# LOGICA_NAO.net
KiCad netlist of a schematic drawn in EAGLE
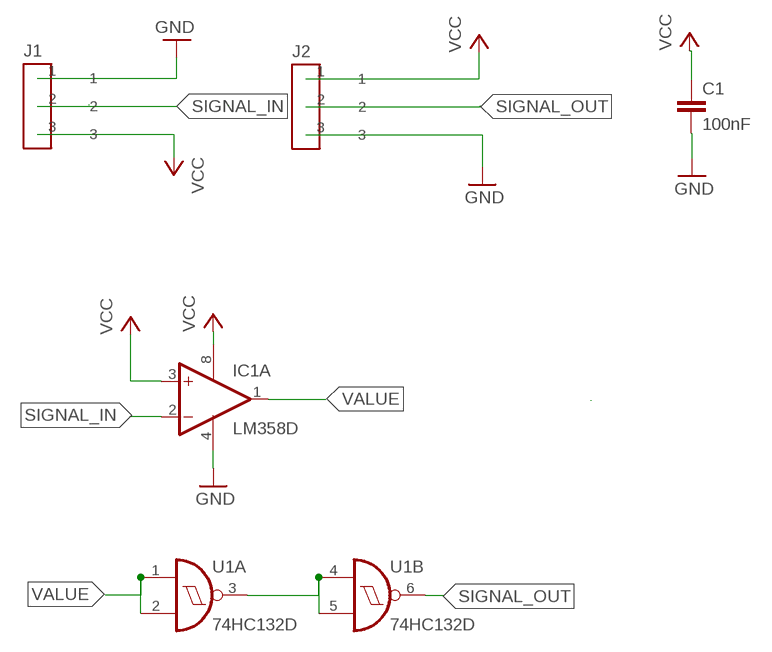
[diagram p0: schematic, sheet 1]

(export (version "E")
  (design (tool "Eeschema 10.0.6"))
  (components
    (comp (ref "C1")
      (value "100nF")
      (footprint "eagle-import:C0805")
      (libsource (lib "eagle-import") (part "C-EUC0805"))
    )
    (comp (ref "IC1")
      (value "LM358D")
      (footprint "eagle-import:SO08")
      (libsource (lib "eagle-import") (part "LM358D"))
    )
    (comp (ref "J1")
      (value "CONECTOR_MACHO")
      (footprint "eagle-import:3CONECTOR")
      (libsource (lib "eagle-import") (part "CONECTOR_MACHO"))
    )
    (comp (ref "J2")
      (value "CONECTOR_FEMEA")
      (footprint "eagle-import:3CONECTOR")
      (libsource (lib "eagle-import") (part "CONECTOR_FEMEA"))
    )
    (comp (ref "U1")
      (value "74HC132D")
      (footprint "eagle-import:SO14")
      (libsource (lib "eagle-import") (part "74132DHC"))
    )
  )
  (nets
    (net (code "1") (name "GND") (class "Default")
      (node (ref "C1") (pin "2") (pinfunction "2_2") (pintype "passive"))
      (node (ref "IC1") (pin "4") (pinfunction "V-_4") (pintype "power_in"))
      (node (ref "J1") (pin "1") (pinfunction "1_1") (pintype "bidirectional"))
      (node (ref "J2") (pin "3") (pinfunction "3_3") (pintype "bidirectional"))
    )
    (net (code "2") (name "Net-(U1A-O)") (class "Default")
      (node (ref "U1") (pin "3") (pinfunction "O_3") (pintype "output"))
      (node (ref "U1") (pin "4") (pinfunction "I0_4") (pintype "input"))
      (node (ref "U1") (pin "5") (pinfunction "I1_5") (pintype "input"))
    )
    (net (code "3") (name "SIGNAL_IN") (class "Default")
      (node (ref "IC1") (pin "2") (pinfunction "-IN_2") (pintype "input"))
      (node (ref "J1") (pin "2") (pinfunction "2_2") (pintype "bidirectional"))
    )
    (net (code "4") (name "SIGNAL_OUT") (class "Default")
      (node (ref "J2") (pin "2") (pinfunction "2_2") (pintype "bidirectional"))
      (node (ref "U1") (pin "6") (pinfunction "O_6") (pintype "output"))
    )
    (net (code "5") (name "VALUE") (class "Default")
      (node (ref "IC1") (pin "1") (pinfunction "OUT_1") (pintype "output"))
      (node (ref "U1") (pin "1") (pinfunction "I0_1") (pintype "input"))
      (node (ref "U1") (pin "2") (pinfunction "I1_2") (pintype "input"))
    )
    (net (code "6") (name "VCC") (class "Default")
      (node (ref "C1") (pin "1") (pinfunction "1_1") (pintype "passive"))
      (node (ref "IC1") (pin "3") (pinfunction "+IN_3") (pintype "input"))
      (node (ref "IC1") (pin "8") (pinfunction "V+_8") (pintype "power_in"))
      (node (ref "J1") (pin "3") (pinfunction "3_3") (pintype "bidirectional"))
      (node (ref "J2") (pin "1") (pinfunction "1_1") (pintype "bidirectional"))
    )
  )
)
